# usb_ir_tester.net
KiCad netlist of a schematic drawn in EAGLE
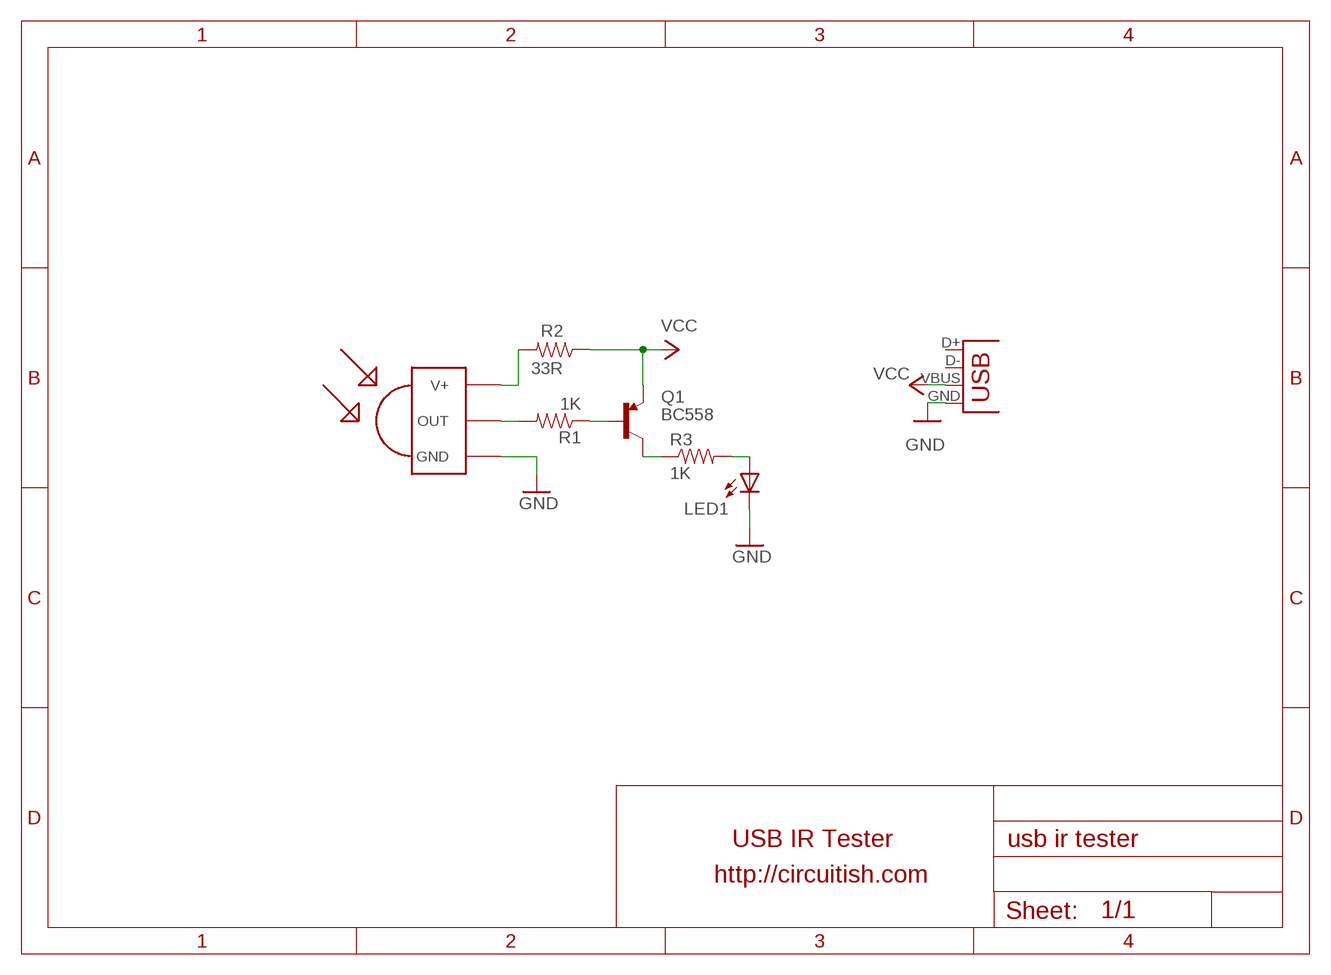
[diagram p0: schematic, sheet 1]

(export (version "E")
  (design (tool "Eeschema 10.0.6"))
  (components
    (comp (ref "LED1")
      (value "LED0603")
      (footprint "eagle-import:LED-0603")
      (libsource (lib "eagle-import") (part "LED0603"))
    )
    (comp (ref "Q1")
      (value "BC558")
      (footprint "eagle-import:SOT23-3")
      (libsource (lib "eagle-import") (part "TRANSISTOR_PNPSMD"))
    )
    (comp (ref "R1")
      (value "1K")
      (footprint "eagle-import:0805")
      (libsource (lib "eagle-import") (part "RESISTOR0805-RES"))
    )
    (comp (ref "R2")
      (value "33R")
      (footprint "eagle-import:0805")
      (libsource (lib "eagle-import") (part "RESISTOR0805-RES"))
    )
    (comp (ref "R3")
      (value "1K")
      (footprint "eagle-import:0805")
      (libsource (lib "eagle-import") (part "RESISTOR0805-RES"))
    )
    (comp (ref "U$1")
      (value "TSOP1738")
      (footprint "eagle-import:TSOP17XX")
      (libsource (lib "eagle-import") (part "TSOP1738"))
    )
    (comp (ref "USB")
      (value "USB Mini")
      (footprint "eagle-import:USB-MINIB-NOSTOP")
      (libsource (lib "eagle-import") (part "USB-SMD-NS"))
    )
  )
  (nets
    (net (code "1") (name "GND") (class "Default")
      (node (ref "LED1") (pin "C") (pinfunction "C_C") (pintype "passive"))
      (node (ref "U$1") (pin "GND") (pinfunction "GND_GND") (pintype "bidirectional"))
      (node (ref "USB") (pin "GND") (pinfunction "GND_GND") (pintype "bidirectional"))
    )
    (net (code "2") (name "Net-(LED1-PadA)") (class "Default")
      (node (ref "LED1") (pin "A") (pinfunction "A_A") (pintype "passive"))
      (node (ref "R3") (pin "2") (pinfunction "2_2") (pintype "passive"))
    )
    (net (code "3") (name "Net-(Q1-B)") (class "Default")
      (node (ref "Q1") (pin "1") (pinfunction "B_1") (pintype "passive"))
      (node (ref "R1") (pin "1") (pinfunction "1_1") (pintype "passive"))
    )
    (net (code "4") (name "Net-(Q1-C)") (class "Default")
      (node (ref "Q1") (pin "3") (pinfunction "C_3") (pintype "passive"))
      (node (ref "R3") (pin "1") (pinfunction "1_1") (pintype "passive"))
    )
    (net (code "5") (name "Net-(R1-Pad2)") (class "Default")
      (node (ref "R1") (pin "2") (pinfunction "2_2") (pintype "passive"))
      (node (ref "U$1") (pin "OUT") (pinfunction "OUT_OUT") (pintype "bidirectional"))
    )
    (net (code "6") (name "Net-(R2-Pad2)") (class "Default")
      (node (ref "R2") (pin "2") (pinfunction "2_2") (pintype "passive"))
      (node (ref "U$1") (pin "V+") (pinfunction "V+_V+") (pintype "bidirectional"))
    )
    (net (code "7") (name "VCC") (class "Default")
      (node (ref "Q1") (pin "2") (pinfunction "E_2") (pintype "passive"))
      (node (ref "R2") (pin "1") (pinfunction "1_1") (pintype "passive"))
      (node (ref "USB") (pin "VBUS") (pinfunction "VBUS_VBUS") (pintype "bidirectional"))
    )
    (net (code "8") (name "unconnected-(USB-PadD+)") (class "Default")
      (node (ref "USB") (pin "D+") (pinfunction "D+_D+") (pintype "bidirectional"))
    )
    (net (code "9") (name "unconnected-(USB-PadD-)") (class "Default")
      (node (ref "USB") (pin "D-") (pinfunction "D-_D-") (pintype "bidirectional"))
    )
  )
)
